# Submarine.net
KiCad netlist of a schematic drawn in Altium Designer
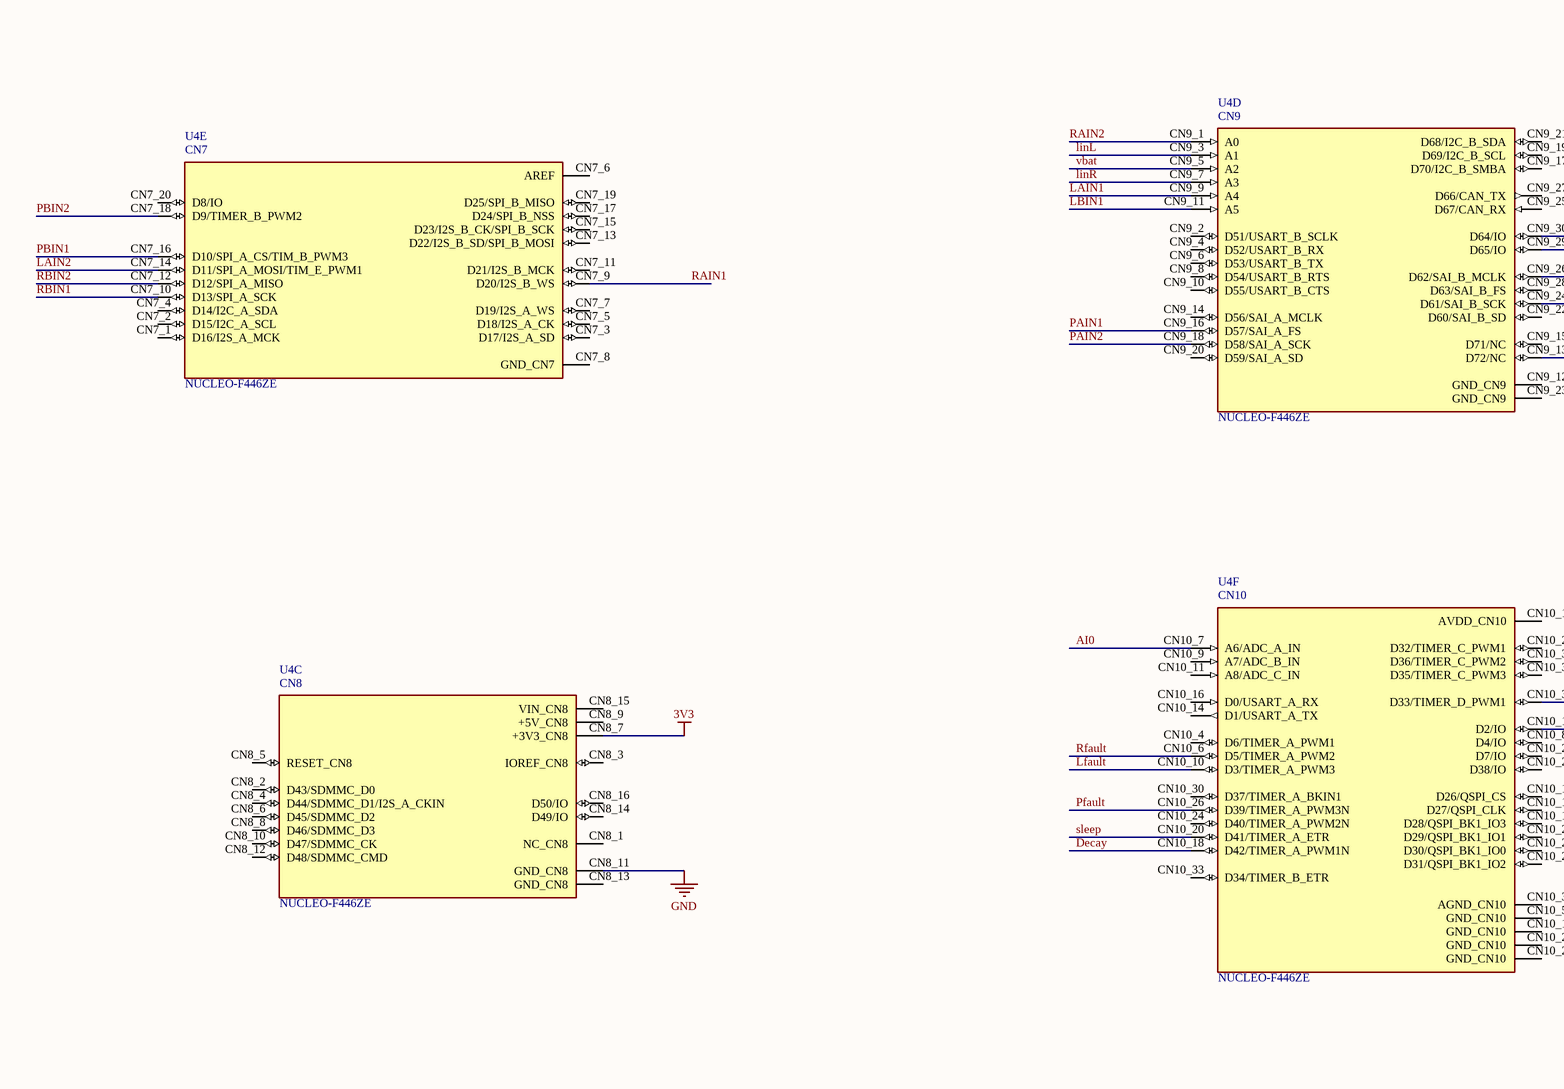
[diagram p0: Submarine.SchDoc, top left]
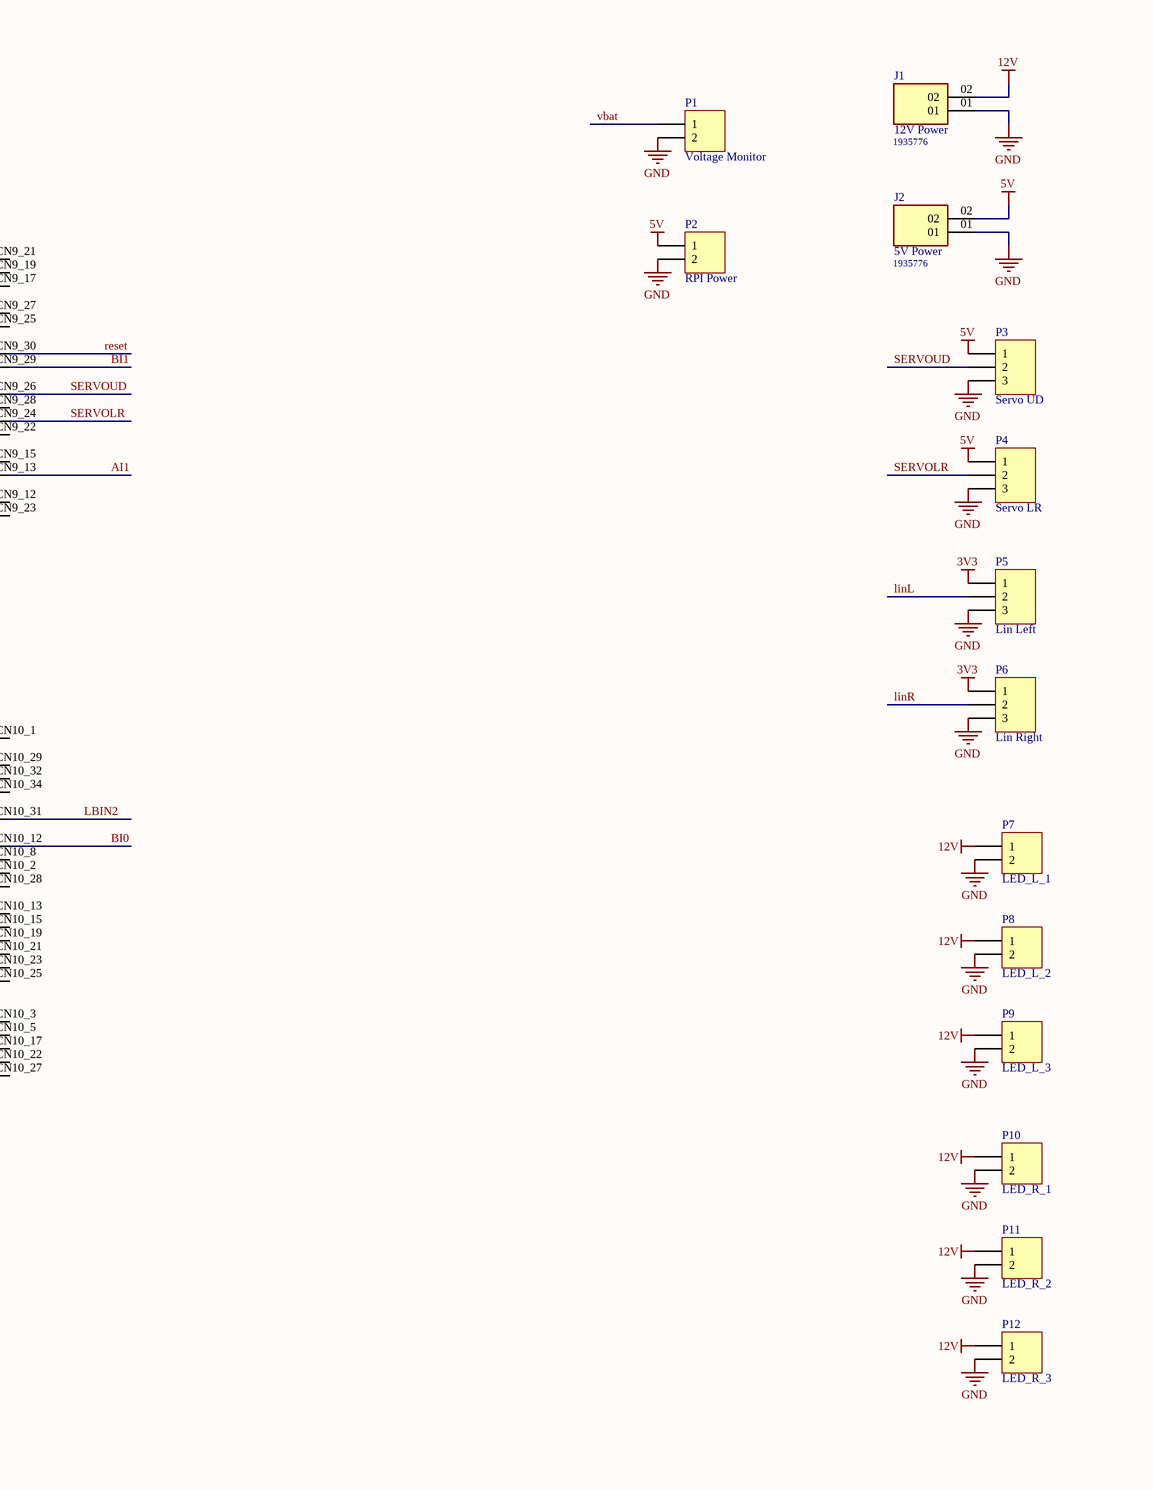
[diagram p1: Submarine.SchDoc, top middle]
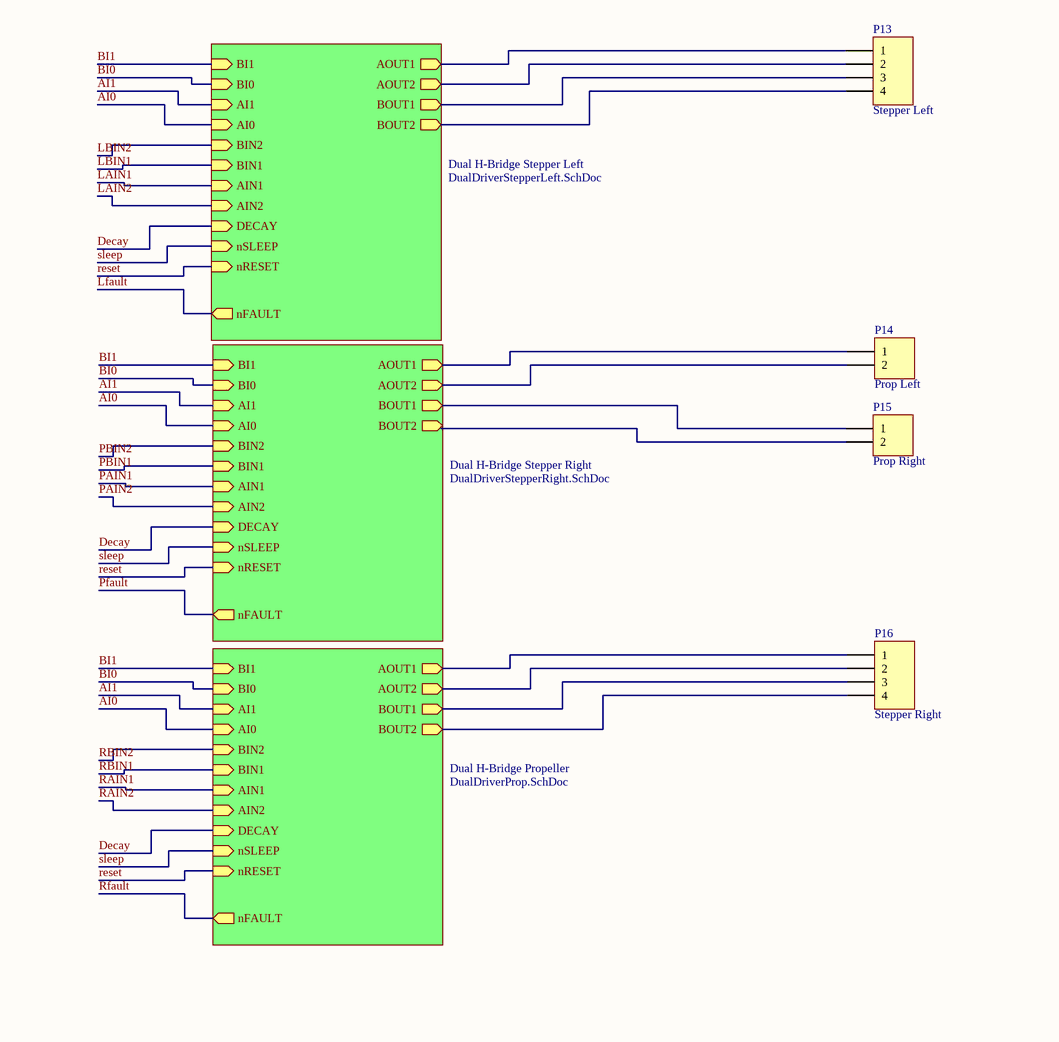
[diagram p2: Submarine.SchDoc, bottom middle]
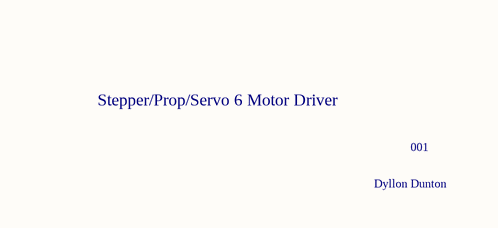
[diagram p3: Submarine.SchDoc, bottom right]

(export (version "E")
  (design (tool "Eeschema 10.0.6"))
  (components
    (comp (ref "J1")
      (value "12V Power")
      (footprint "PHOENIX_1935776")
      (fields (field (name "MP") "1935776"))
      (libsource (lib "1935776") (part "1935776"))
    )
    (comp (ref "J2")
      (value "5V Power")
      (footprint "PHOENIX_1935776")
      (fields (field (name "MP") "1935776"))
      (libsource (lib "1935776") (part "1935776"))
    )
    (comp (ref "P1")
      (value "Voltage Monitor")
      (footprint "HDR1X2")
      (description "Header, 2-Pin")
      (fields (field (name "PUBLISHER") "Altium Limited"))
      (libsource (lib "Miscellaneous Connectors") (part "Header 2"))
    )
    (comp (ref "P2")
      (value "RPI Power")
      (footprint "HDR1X2")
      (description "Header, 2-Pin")
      (fields (field (name "PUBLISHER") "Altium Limited"))
      (libsource (lib "Miscellaneous Connectors") (part "Header 2"))
    )
    (comp (ref "P3")
      (value "Servo UD")
      (footprint "HDR1X3")
      (description "Header, 3-Pin")
      (fields (field (name "PUBLISHER") "Altium Limited"))
      (libsource (lib "Miscellaneous Connectors") (part "Header 3"))
    )
    (comp (ref "P4")
      (value "Servo LR")
      (footprint "HDR1X3")
      (description "Header, 3-Pin")
      (fields (field (name "PUBLISHER") "Altium Limited"))
      (libsource (lib "Miscellaneous Connectors") (part "Header 3"))
    )
    (comp (ref "P5")
      (value "Lin Left")
      (footprint "HDR1X3")
      (description "Header, 3-Pin")
      (fields (field (name "PUBLISHER") "Altium Limited"))
      (libsource (lib "Miscellaneous Connectors") (part "Header 3"))
    )
    (comp (ref "P6")
      (value "Lin Right")
      (footprint "HDR1X3")
      (description "Header, 3-Pin")
      (fields (field (name "PUBLISHER") "Altium Limited"))
      (libsource (lib "Miscellaneous Connectors") (part "Header 3"))
    )
    (comp (ref "P7")
      (value "LED_L_1")
      (footprint "HDR1X2")
      (description "Header, 2-Pin")
      (fields (field (name "PUBLISHER") "Altium Limited"))
      (libsource (lib "Miscellaneous Connectors") (part "Header 2"))
    )
    (comp (ref "P8")
      (value "LED_L_2")
      (footprint "HDR1X2")
      (description "Header, 2-Pin")
      (fields (field (name "PUBLISHER") "Altium Limited"))
      (libsource (lib "Miscellaneous Connectors") (part "Header 2"))
    )
    (comp (ref "P9")
      (value "LED_L_3")
      (footprint "HDR1X2")
      (description "Header, 2-Pin")
      (fields (field (name "PUBLISHER") "Altium Limited"))
      (libsource (lib "Miscellaneous Connectors") (part "Header 2"))
    )
    (comp (ref "P10")
      (value "LED_R_1")
      (footprint "HDR1X2")
      (description "Header, 2-Pin")
      (fields (field (name "PUBLISHER") "Altium Limited"))
      (libsource (lib "Miscellaneous Connectors") (part "Header 2"))
    )
    (comp (ref "P11")
      (value "LED_R_2")
      (footprint "HDR1X2")
      (description "Header, 2-Pin")
      (fields (field (name "PUBLISHER") "Altium Limited"))
      (libsource (lib "Miscellaneous Connectors") (part "Header 2"))
    )
    (comp (ref "P12")
      (value "LED_R_3")
      (footprint "HDR1X2")
      (description "Header, 2-Pin")
      (fields (field (name "PUBLISHER") "Altium Limited"))
      (libsource (lib "Miscellaneous Connectors") (part "Header 2"))
    )
    (comp (ref "P13")
      (value "Stepper Left")
      (footprint "HDR1X4")
      (description "Header, 4-Pin")
      (fields (field (name "PUBLISHER") "Altium Limited"))
      (libsource (lib "Miscellaneous Connectors") (part "Header 4"))
    )
    (comp (ref "P14")
      (value "Prop Left")
      (footprint "HDR1X2")
      (description "Header, 2-Pin")
      (fields (field (name "PUBLISHER") "Altium Limited"))
      (libsource (lib "Miscellaneous Connectors") (part "Header 2"))
    )
    (comp (ref "P15")
      (value "Prop Right")
      (footprint "HDR1X2")
      (description "Header, 2-Pin")
      (fields (field (name "PUBLISHER") "Altium Limited"))
      (libsource (lib "Miscellaneous Connectors") (part "Header 2"))
    )
    (comp (ref "P16")
      (value "Stepper Right")
      (footprint "HDR1X4")
      (description "Header, 4-Pin")
      (fields (field (name "PUBLISHER") "Altium Limited"))
      (libsource (lib "Miscellaneous Connectors") (part "Header 4"))
    )
    (comp (ref "U4")
      (value "NUCLEO-F446ZE")
      (footprint "MODULE_NUCLEO-F446ZE")
      (fields (field (name "MF") "STMicroelectronics"))
      (libsource (lib "NUCLEO-F446ZE") (part "NUCLEO-F446ZE"))
    )
  )
  (nets
    (net (code "1") (name "/AI0") (class "Default")
      (node (ref "U4") (pin "CN10_7") (pinfunction "A6/ADC_A_IN_CN10_7") (pintype "input"))
    )
    (net (code "2") (name "/AI1") (class "Default")
      (node (ref "U4") (pin "CN9_13") (pinfunction "D72/NC_CN9_13") (pintype "bidirectional"))
    )
    (net (code "3") (name "/AOUT1") (class "Default")
      (node (ref "P16") (pin "1") (pinfunction "1_1") (pintype "passive"))
    )
    (net (code "4") (name "/AOUT1_1") (class "Default")
      (node (ref "P13") (pin "1") (pinfunction "1_1") (pintype "passive"))
    )
    (net (code "5") (name "/AOUT1_2") (class "Default")
      (node (ref "P14") (pin "1") (pinfunction "1_1") (pintype "passive"))
    )
    (net (code "6") (name "/AOUT2") (class "Default")
      (node (ref "P16") (pin "2") (pinfunction "2_2") (pintype "passive"))
    )
    (net (code "7") (name "/AOUT2_1") (class "Default")
      (node (ref "P13") (pin "2") (pinfunction "2_2") (pintype "passive"))
    )
    (net (code "8") (name "/AOUT2_2") (class "Default")
      (node (ref "P14") (pin "2") (pinfunction "2_2") (pintype "passive"))
    )
    (net (code "9") (name "/BI0") (class "Default")
      (node (ref "U4") (pin "CN10_12") (pinfunction "D2/IO_CN10_12") (pintype "bidirectional"))
    )
    (net (code "10") (name "/BI1") (class "Default")
      (node (ref "U4") (pin "CN9_29") (pinfunction "D65/IO_CN9_29") (pintype "bidirectional"))
    )
    (net (code "11") (name "/BOUT1") (class "Default")
      (node (ref "P15") (pin "1") (pinfunction "1_1") (pintype "passive"))
    )
    (net (code "12") (name "/BOUT1_1") (class "Default")
      (node (ref "P13") (pin "3") (pinfunction "3_3") (pintype "passive"))
    )
    (net (code "13") (name "/BOUT1_2") (class "Default")
      (node (ref "P16") (pin "3") (pinfunction "3_3") (pintype "passive"))
    )
    (net (code "15") (name "/BOUT2_1") (class "Default")
      (node (ref "P13") (pin "4") (pinfunction "4_4") (pintype "passive"))
    )
    (net (code "16") (name "/BOUT2_2") (class "Default")
      (node (ref "P16") (pin "4") (pinfunction "4_4") (pintype "passive"))
    )
    (net (code "17") (name "/Decay") (class "Default")
      (node (ref "U4") (pin "CN10_18") (pinfunction "D42/TIMER_A_PWM1N_CN10_18") (pintype "bidirectional"))
    )
    (net (code "18") (name "/LAIN1") (class "Default")
      (node (ref "U4") (pin "CN9_9") (pinfunction "A4_CN9_9") (pintype "input"))
    )
    (net (code "19") (name "/LAIN2") (class "Default")
      (node (ref "U4") (pin "CN7_14") (pinfunction "D11/SPI_A_MOSI/TIM_E_PWM1_CN7_14") (pintype "bidirectional"))
    )
    (net (code "20") (name "/LBIN1") (class "Default")
      (node (ref "U4") (pin "CN9_11") (pinfunction "A5_CN9_11") (pintype "input"))
    )
    (net (code "21") (name "/LBIN2") (class "Default")
      (node (ref "U4") (pin "CN10_31") (pinfunction "D33/TIMER_D_PWM1_CN10_31") (pintype "bidirectional"))
    )
    (net (code "22") (name "/Lfault") (class "Default")
      (node (ref "U4") (pin "CN10_10") (pinfunction "D3/TIMER_A_PWM3_CN10_10") (pintype "bidirectional"))
    )
    (net (code "23") (name "/PAIN1") (class "Default")
      (node (ref "U4") (pin "CN9_16") (pinfunction "D57/SAI_A_FS_CN9_16") (pintype "bidirectional"))
    )
    (net (code "24") (name "/PAIN2") (class "Default")
      (node (ref "U4") (pin "CN9_18") (pinfunction "D58/SAI_A_SCK_CN9_18") (pintype "bidirectional"))
    )
    (net (code "25") (name "/PBIN1") (class "Default")
      (node (ref "U4") (pin "CN7_16") (pinfunction "D10/SPI_A_CS/TIM_B_PWM3_CN7_16") (pintype "bidirectional"))
    )
    (net (code "26") (name "/PBIN2") (class "Default")
      (node (ref "U4") (pin "CN7_18") (pinfunction "D9/TIMER_B_PWM2_CN7_18") (pintype "bidirectional"))
    )
    (net (code "27") (name "/Pfault") (class "Default")
      (node (ref "U4") (pin "CN10_26") (pinfunction "D39/TIMER_A_PWM3N_CN10_26") (pintype "bidirectional"))
    )
    (net (code "28") (name "/RAIN1") (class "Default")
      (node (ref "U4") (pin "CN7_9") (pinfunction "D20/I2S_B_WS_CN7_9") (pintype "bidirectional"))
    )
    (net (code "29") (name "/RAIN2") (class "Default")
      (node (ref "U4") (pin "CN9_1") (pinfunction "A0_CN9_1") (pintype "input"))
    )
    (net (code "30") (name "/RBIN1") (class "Default")
      (node (ref "U4") (pin "CN7_10") (pinfunction "D13/SPI_A_SCK_CN7_10") (pintype "bidirectional"))
    )
    (net (code "31") (name "/RBIN2") (class "Default")
      (node (ref "U4") (pin "CN7_12") (pinfunction "D12/SPI_A_MISO_CN7_12") (pintype "bidirectional"))
    )
    (net (code "32") (name "/Rfault") (class "Default")
      (node (ref "U4") (pin "CN10_6") (pinfunction "D5/TIMER_A_PWM2_CN10_6") (pintype "bidirectional"))
    )
    (net (code "33") (name "/SERVOLR") (class "Default")
      (node (ref "P4") (pin "2") (pinfunction "2_2") (pintype "passive"))
      (node (ref "U4") (pin "CN9_24") (pinfunction "D61/SAI_B_SCK_CN9_24") (pintype "bidirectional"))
    )
    (net (code "34") (name "/SERVOUD") (class "Default")
      (node (ref "P3") (pin "2") (pinfunction "2_2") (pintype "passive"))
      (node (ref "U4") (pin "CN9_26") (pinfunction "D62/SAI_B_MCLK_CN9_26") (pintype "bidirectional"))
    )
    (net (code "35") (name "/linL") (class "Default")
      (node (ref "P5") (pin "2") (pinfunction "2_2") (pintype "passive"))
      (node (ref "U4") (pin "CN9_3") (pinfunction "A1_CN9_3") (pintype "input"))
    )
    (net (code "36") (name "/linR") (class "Default")
      (node (ref "P6") (pin "2") (pinfunction "2_2") (pintype "passive"))
      (node (ref "U4") (pin "CN9_7") (pinfunction "A3_CN9_7") (pintype "input"))
    )
    (net (code "37") (name "/reset") (class "Default")
      (node (ref "U4") (pin "CN9_30") (pinfunction "D64/IO_CN9_30") (pintype "bidirectional"))
    )
    (net (code "38") (name "/sleep") (class "Default")
      (node (ref "U4") (pin "CN10_20") (pinfunction "D41/TIMER_A_ETR_CN10_20") (pintype "bidirectional"))
    )
    (net (code "39") (name "/vbat") (class "Default")
      (node (ref "P1") (pin "1") (pinfunction "1_1") (pintype "passive"))
      (node (ref "U4") (pin "CN9_5") (pinfunction "A2_CN9_5") (pintype "input"))
    )
    (net (code "40") (name "3V3") (class "Default")
      (node (ref "P5") (pin "1") (pinfunction "1_1") (pintype "passive"))
      (node (ref "P6") (pin "1") (pinfunction "1_1") (pintype "passive"))
      (node (ref "U4") (pin "CN8_7") (pinfunction "+3V3_CN8_CN8_7") (pintype "power_in"))
    )
    (net (code "41") (name "5V") (class "Default")
      (node (ref "J2") (pin "02") (pinfunction "02_02") (pintype "passive"))
      (node (ref "P2") (pin "1") (pinfunction "1_1") (pintype "passive"))
      (node (ref "P3") (pin "1") (pinfunction "1_1") (pintype "passive"))
      (node (ref "P4") (pin "1") (pinfunction "1_1") (pintype "passive"))
    )
    (net (code "42") (name "12V") (class "Default")
      (node (ref "J1") (pin "02") (pinfunction "02_02") (pintype "passive"))
      (node (ref "P10") (pin "1") (pinfunction "1_1") (pintype "passive"))
      (node (ref "P11") (pin "1") (pinfunction "1_1") (pintype "passive"))
      (node (ref "P12") (pin "1") (pinfunction "1_1") (pintype "passive"))
      (node (ref "P7") (pin "1") (pinfunction "1_1") (pintype "passive"))
      (node (ref "P8") (pin "1") (pinfunction "1_1") (pintype "passive"))
      (node (ref "P9") (pin "1") (pinfunction "1_1") (pintype "passive"))
    )
    (net (code "43") (name "GND") (class "Default")
      (node (ref "J1") (pin "01") (pinfunction "01_01") (pintype "passive"))
      (node (ref "J2") (pin "01") (pinfunction "01_01") (pintype "passive"))
      (node (ref "P1") (pin "2") (pinfunction "2_2") (pintype "passive"))
      (node (ref "P10") (pin "2") (pinfunction "2_2") (pintype "passive"))
      (node (ref "P11") (pin "2") (pinfunction "2_2") (pintype "passive"))
      (node (ref "P12") (pin "2") (pinfunction "2_2") (pintype "passive"))
      (node (ref "P2") (pin "2") (pinfunction "2_2") (pintype "passive"))
      (node (ref "P3") (pin "3") (pinfunction "3_3") (pintype "passive"))
      (node (ref "P4") (pin "3") (pinfunction "3_3") (pintype "passive"))
      (node (ref "P5") (pin "3") (pinfunction "3_3") (pintype "passive"))
      (node (ref "P6") (pin "3") (pinfunction "3_3") (pintype "passive"))
      (node (ref "P7") (pin "2") (pinfunction "2_2") (pintype "passive"))
      (node (ref "P8") (pin "2") (pinfunction "2_2") (pintype "passive"))
      (node (ref "P9") (pin "2") (pinfunction "2_2") (pintype "passive"))
      (node (ref "U4") (pin "CN8_11") (pinfunction "GND_CN8_CN8_11") (pintype "power_in"))
    )
    (net (code "44") (name "unconnected-(P15-Pad2)") (class "Default")
      (node (ref "P15") (pin "2") (pinfunction "2_2") (pintype "passive"))
    )
    (net (code "45") (name "unconnected-(U4C-+5V_CN8-PadCN8_9)") (class "Default")
      (node (ref "U4") (pin "CN8_9") (pinfunction "+5V_CN8_CN8_9") (pintype "power_in"))
    )
    (net (code "46") (name "unconnected-(U4C-D43{slash}SDMMC_D0-PadCN8_2)") (class "Default")
      (node (ref "U4") (pin "CN8_2") (pinfunction "D43/SDMMC_D0_CN8_2") (pintype "bidirectional"))
    )
    (net (code "47") (name "unconnected-(U4C-D44{slash}SDMMC_D1{slash}I2S_A_CKIN-PadCN8_4)") (class "Default")
      (node (ref "U4") (pin "CN8_4") (pinfunction "D44/SDMMC_D1/I2S_A_CKIN_CN8_4") (pintype "bidirectional"))
    )
    (net (code "48") (name "unconnected-(U4C-D45{slash}SDMMC_D2-PadCN8_6)") (class "Default")
      (node (ref "U4") (pin "CN8_6") (pinfunction "D45/SDMMC_D2_CN8_6") (pintype "bidirectional"))
    )
    (net (code "49") (name "unconnected-(U4C-D46{slash}SDMMC_D3-PadCN8_8)") (class "Default")
      (node (ref "U4") (pin "CN8_8") (pinfunction "D46/SDMMC_D3_CN8_8") (pintype "bidirectional"))
    )
    (net (code "50") (name "unconnected-(U4C-D47{slash}SDMMC_CK-PadCN8_10)") (class "Default")
      (node (ref "U4") (pin "CN8_10") (pinfunction "D47/SDMMC_CK_CN8_10") (pintype "bidirectional"))
    )
    (net (code "51") (name "unconnected-(U4C-D48{slash}SDMMC_CMD-PadCN8_12)") (class "Default")
      (node (ref "U4") (pin "CN8_12") (pinfunction "D48/SDMMC_CMD_CN8_12") (pintype "bidirectional"))
    )
    (net (code "52") (name "unconnected-(U4C-D49{slash}IO-PadCN8_14)") (class "Default")
      (node (ref "U4") (pin "CN8_14") (pinfunction "D49/IO_CN8_14") (pintype "bidirectional"))
    )
    (net (code "53") (name "unconnected-(U4C-D50{slash}IO-PadCN8_16)") (class "Default")
      (node (ref "U4") (pin "CN8_16") (pinfunction "D50/IO_CN8_16") (pintype "bidirectional"))
    )
    (net (code "54") (name "unconnected-(U4C-GND_CN8-PadCN8_13)") (class "Default")
      (node (ref "U4") (pin "CN8_13") (pinfunction "GND_CN8_CN8_13") (pintype "power_in"))
    )
    (net (code "55") (name "unconnected-(U4C-IOREF_CN8-PadCN8_3)") (class "Default")
      (node (ref "U4") (pin "CN8_3") (pinfunction "IOREF_CN8_CN8_3") (pintype "bidirectional"))
    )
    (net (code "56") (name "unconnected-(U4C-NC_CN8-PadCN8_1)") (class "Default")
      (node (ref "U4") (pin "CN8_1") (pinfunction "NC_CN8_CN8_1") (pintype "passive"))
    )
    (net (code "57") (name "unconnected-(U4C-RESET_CN8-PadCN8_5)") (class "Default")
      (node (ref "U4") (pin "CN8_5") (pinfunction "RESET_CN8_CN8_5") (pintype "bidirectional"))
    )
    (net (code "58") (name "unconnected-(U4C-VIN_CN8-PadCN8_15)") (class "Default")
      (node (ref "U4") (pin "CN8_15") (pinfunction "VIN_CN8_CN8_15") (pintype "power_in"))
    )
    (net (code "59") (name "unconnected-(U4D-D51{slash}USART_B_SCLK-PadCN9_2)") (class "Default")
      (node (ref "U4") (pin "CN9_2") (pinfunction "D51/USART_B_SCLK_CN9_2") (pintype "bidirectional"))
    )
    (net (code "60") (name "unconnected-(U4D-D52{slash}USART_B_RX-PadCN9_4)") (class "Default")
      (node (ref "U4") (pin "CN9_4") (pinfunction "D52/USART_B_RX_CN9_4") (pintype "bidirectional"))
    )
    (net (code "61") (name "unconnected-(U4D-D53{slash}USART_B_TX-PadCN9_6)") (class "Default")
      (node (ref "U4") (pin "CN9_6") (pinfunction "D53/USART_B_TX_CN9_6") (pintype "bidirectional"))
    )
    (net (code "62") (name "unconnected-(U4D-D54{slash}USART_B_RTS-PadCN9_8)") (class "Default")
      (node (ref "U4") (pin "CN9_8") (pinfunction "D54/USART_B_RTS_CN9_8") (pintype "bidirectional"))
    )
    (net (code "63") (name "unconnected-(U4D-D55{slash}USART_B_CTS-PadCN9_10)") (class "Default")
      (node (ref "U4") (pin "CN9_10") (pinfunction "D55/USART_B_CTS_CN9_10") (pintype "bidirectional"))
    )
    (net (code "64") (name "unconnected-(U4D-D56{slash}SAI_A_MCLK-PadCN9_14)") (class "Default")
      (node (ref "U4") (pin "CN9_14") (pinfunction "D56/SAI_A_MCLK_CN9_14") (pintype "bidirectional"))
    )
    (net (code "65") (name "unconnected-(U4D-D59{slash}SAI_A_SD-PadCN9_20)") (class "Default")
      (node (ref "U4") (pin "CN9_20") (pinfunction "D59/SAI_A_SD_CN9_20") (pintype "bidirectional"))
    )
    (net (code "66") (name "unconnected-(U4D-D60{slash}SAI_B_SD-PadCN9_22)") (class "Default")
      (node (ref "U4") (pin "CN9_22") (pinfunction "D60/SAI_B_SD_CN9_22") (pintype "bidirectional"))
    )
    (net (code "67") (name "unconnected-(U4D-D63{slash}SAI_B_FS-PadCN9_28)") (class "Default")
      (node (ref "U4") (pin "CN9_28") (pinfunction "D63/SAI_B_FS_CN9_28") (pintype "bidirectional"))
    )
    (net (code "68") (name "unconnected-(U4D-D66{slash}CAN_TX-PadCN9_27)") (class "Default")
      (node (ref "U4") (pin "CN9_27") (pinfunction "D66/CAN_TX_CN9_27") (pintype "output"))
    )
    (net (code "69") (name "unconnected-(U4D-D67{slash}CAN_RX-PadCN9_25)") (class "Default")
      (node (ref "U4") (pin "CN9_25") (pinfunction "D67/CAN_RX_CN9_25") (pintype "input"))
    )
    (net (code "70") (name "unconnected-(U4D-D68{slash}I2C_B_SDA-PadCN9_21)") (class "Default")
      (node (ref "U4") (pin "CN9_21") (pinfunction "D68/I2C_B_SDA_CN9_21") (pintype "bidirectional"))
    )
    (net (code "71") (name "unconnected-(U4D-D69{slash}I2C_B_SCL-PadCN9_19)") (class "Default")
      (node (ref "U4") (pin "CN9_19") (pinfunction "D69/I2C_B_SCL_CN9_19") (pintype "bidirectional"))
    )
    (net (code "72") (name "unconnected-(U4D-D70{slash}I2C_B_SMBA-PadCN9_17)") (class "Default")
      (node (ref "U4") (pin "CN9_17") (pinfunction "D70/I2C_B_SMBA_CN9_17") (pintype "bidirectional"))
    )
    (net (code "73") (name "unconnected-(U4D-D71{slash}NC-PadCN9_15)") (class "Default")
      (node (ref "U4") (pin "CN9_15") (pinfunction "D71/NC_CN9_15") (pintype "bidirectional"))
    )
    (net (code "74") (name "unconnected-(U4D-GND_CN9-PadCN9_12)") (class "Default")
      (node (ref "U4") (pin "CN9_12") (pinfunction "GND_CN9_CN9_12") (pintype "power_in"))
    )
    (net (code "75") (name "unconnected-(U4D-GND_CN9-PadCN9_23)") (class "Default")
      (node (ref "U4") (pin "CN9_23") (pinfunction "GND_CN9_CN9_23") (pintype "power_in"))
    )
    (net (code "76") (name "unconnected-(U4E-AREF-PadCN7_6)") (class "Default")
      (node (ref "U4") (pin "CN7_6") (pinfunction "AREF_CN7_6") (pintype "power_in"))
    )
    (net (code "77") (name "unconnected-(U4E-D8{slash}IO-PadCN7_20)") (class "Default")
      (node (ref "U4") (pin "CN7_20") (pinfunction "D8/IO_CN7_20") (pintype "bidirectional"))
    )
    (net (code "78") (name "unconnected-(U4E-D14{slash}I2C_A_SDA-PadCN7_4)") (class "Default")
      (node (ref "U4") (pin "CN7_4") (pinfunction "D14/I2C_A_SDA_CN7_4") (pintype "bidirectional"))
    )
    (net (code "79") (name "unconnected-(U4E-D15{slash}I2C_A_SCL-PadCN7_2)") (class "Default")
      (node (ref "U4") (pin "CN7_2") (pinfunction "D15/I2C_A_SCL_CN7_2") (pintype "bidirectional"))
    )
    (net (code "80") (name "unconnected-(U4E-D16{slash}I2S_A_MCK-PadCN7_1)") (class "Default")
      (node (ref "U4") (pin "CN7_1") (pinfunction "D16/I2S_A_MCK_CN7_1") (pintype "bidirectional"))
    )
    (net (code "81") (name "unconnected-(U4E-D17{slash}I2S_A_SD-PadCN7_3)") (class "Default")
      (node (ref "U4") (pin "CN7_3") (pinfunction "D17/I2S_A_SD_CN7_3") (pintype "bidirectional"))
    )
    (net (code "82") (name "unconnected-(U4E-D18{slash}I2S_A_CK-PadCN7_5)") (class "Default")
      (node (ref "U4") (pin "CN7_5") (pinfunction "D18/I2S_A_CK_CN7_5") (pintype "bidirectional"))
    )
    (net (code "83") (name "unconnected-(U4E-D19{slash}I2S_A_WS-PadCN7_7)") (class "Default")
      (node (ref "U4") (pin "CN7_7") (pinfunction "D19/I2S_A_WS_CN7_7") (pintype "bidirectional"))
    )
    (net (code "84") (name "unconnected-(U4E-D21{slash}I2S_B_MCK-PadCN7_11)") (class "Default")
      (node (ref "U4") (pin "CN7_11") (pinfunction "D21/I2S_B_MCK_CN7_11") (pintype "bidirectional"))
    )
    (net (code "85") (name "unconnected-(U4E-D22{slash}I2S_B_SD{slash}SPI_B_MOSI-PadCN7_13)") (class "Default")
      (node (ref "U4") (pin "CN7_13") (pinfunction "D22/I2S_B_SD/SPI_B_MOSI_CN7_13") (pintype "bidirectional"))
    )
    (net (code "86") (name "unconnected-(U4E-D23{slash}I2S_B_CK{slash}SPI_B_SCK-PadCN7_15)") (class "Default")
      (node (ref "U4") (pin "CN7_15") (pinfunction "D23/I2S_B_CK/SPI_B_SCK_CN7_15") (pintype "bidirectional"))
    )
    (net (code "87") (name "unconnected-(U4E-D24{slash}SPI_B_NSS-PadCN7_17)") (class "Default")
      (node (ref "U4") (pin "CN7_17") (pinfunction "D24/SPI_B_NSS_CN7_17") (pintype "bidirectional"))
    )
    (net (code "88") (name "unconnected-(U4E-D25{slash}SPI_B_MISO-PadCN7_19)") (class "Default")
      (node (ref "U4") (pin "CN7_19") (pinfunction "D25/SPI_B_MISO_CN7_19") (pintype "bidirectional"))
    )
    (net (code "89") (name "unconnected-(U4E-GND_CN7-PadCN7_8)") (class "Default")
      (node (ref "U4") (pin "CN7_8") (pinfunction "GND_CN7_CN7_8") (pintype "power_in"))
    )
    (net (code "90") (name "unconnected-(U4F-A7{slash}ADC_B_IN-PadCN10_9)") (class "Default")
      (node (ref "U4") (pin "CN10_9") (pinfunction "A7/ADC_B_IN_CN10_9") (pintype "input"))
    )
    (net (code "91") (name "unconnected-(U4F-A8{slash}ADC_C_IN-PadCN10_11)") (class "Default")
      (node (ref "U4") (pin "CN10_11") (pinfunction "A8/ADC_C_IN_CN10_11") (pintype "input"))
    )
    (net (code "92") (name "unconnected-(U4F-AGND_CN10-PadCN10_3)") (class "Default")
      (node (ref "U4") (pin "CN10_3") (pinfunction "AGND_CN10_CN10_3") (pintype "power_in"))
    )
    (net (code "93") (name "unconnected-(U4F-AVDD_CN10-PadCN10_1)") (class "Default")
      (node (ref "U4") (pin "CN10_1") (pinfunction "AVDD_CN10_CN10_1") (pintype "power_in"))
    )
    (net (code "94") (name "unconnected-(U4F-D0{slash}USART_A_RX-PadCN10_16)") (class "Default")
      (node (ref "U4") (pin "CN10_16") (pinfunction "D0/USART_A_RX_CN10_16") (pintype "input"))
    )
    (net (code "95") (name "unconnected-(U4F-D1{slash}USART_A_TX-PadCN10_14)") (class "Default")
      (node (ref "U4") (pin "CN10_14") (pinfunction "D1/USART_A_TX_CN10_14") (pintype "output"))
    )
    (net (code "96") (name "unconnected-(U4F-D4{slash}IO-PadCN10_8)") (class "Default")
      (node (ref "U4") (pin "CN10_8") (pinfunction "D4/IO_CN10_8") (pintype "bidirectional"))
    )
    (net (code "97") (name "unconnected-(U4F-D6{slash}TIMER_A_PWM1-PadCN10_4)") (class "Default")
      (node (ref "U4") (pin "CN10_4") (pinfunction "D6/TIMER_A_PWM1_CN10_4") (pintype "bidirectional"))
    )
    (net (code "98") (name "unconnected-(U4F-D7{slash}IO-PadCN10_2)") (class "Default")
      (node (ref "U4") (pin "CN10_2") (pinfunction "D7/IO_CN10_2") (pintype "bidirectional"))
    )
    (net (code "99") (name "unconnected-(U4F-D26{slash}QSPI_CS-PadCN10_13)") (class "Default")
      (node (ref "U4") (pin "CN10_13") (pinfunction "D26/QSPI_CS_CN10_13") (pintype "bidirectional"))
    )
    (net (code "100") (name "unconnected-(U4F-D27{slash}QSPI_CLK-PadCN10_15)") (class "Default")
      (node (ref "U4") (pin "CN10_15") (pinfunction "D27/QSPI_CLK_CN10_15") (pintype "bidirectional"))
    )
    (net (code "101") (name "unconnected-(U4F-D28{slash}QSPI_BK1_IO3-PadCN10_19)") (class "Default")
      (node (ref "U4") (pin "CN10_19") (pinfunction "D28/QSPI_BK1_IO3_CN10_19") (pintype "bidirectional"))
    )
    (net (code "102") (name "unconnected-(U4F-D29{slash}QSPI_BK1_IO1-PadCN10_21)") (class "Default")
      (node (ref "U4") (pin "CN10_21") (pinfunction "D29/QSPI_BK1_IO1_CN10_21") (pintype "bidirectional"))
    )
    (net (code "103") (name "unconnected-(U4F-D30{slash}QSPI_BK1_IO0-PadCN10_23)") (class "Default")
      (node (ref "U4") (pin "CN10_23") (pinfunction "D30/QSPI_BK1_IO0_CN10_23") (pintype "bidirectional"))
    )
    (net (code "104") (name "unconnected-(U4F-D31{slash}QSPI_BK1_IO2-PadCN10_25)") (class "Default")
      (node (ref "U4") (pin "CN10_25") (pinfunction "D31/QSPI_BK1_IO2_CN10_25") (pintype "bidirectional"))
    )
    (net (code "105") (name "unconnected-(U4F-D32{slash}TIMER_C_PWM1-PadCN10_29)") (class "Default")
      (node (ref "U4") (pin "CN10_29") (pinfunction "D32/TIMER_C_PWM1_CN10_29") (pintype "bidirectional"))
    )
    (net (code "106") (name "unconnected-(U4F-D34{slash}TIMER_B_ETR-PadCN10_33)") (class "Default")
      (node (ref "U4") (pin "CN10_33") (pinfunction "D34/TIMER_B_ETR_CN10_33") (pintype "bidirectional"))
    )
    (net (code "107") (name "unconnected-(U4F-D35{slash}TIMER_C_PWM3-PadCN10_34)") (class "Default")
      (node (ref "U4") (pin "CN10_34") (pinfunction "D35/TIMER_C_PWM3_CN10_34") (pintype "bidirectional"))
    )
    (net (code "108") (name "unconnected-(U4F-D36{slash}TIMER_C_PWM2-PadCN10_32)") (class "Default")
      (node (ref "U4") (pin "CN10_32") (pinfunction "D36/TIMER_C_PWM2_CN10_32") (pintype "bidirectional"))
    )
    (net (code "109") (name "unconnected-(U4F-D37{slash}TIMER_A_BKIN1-PadCN10_30)") (class "Default")
      (node (ref "U4") (pin "CN10_30") (pinfunction "D37/TIMER_A_BKIN1_CN10_30") (pintype "bidirectional"))
    )
    (net (code "110") (name "unconnected-(U4F-D38{slash}IO-PadCN10_28)") (class "Default")
      (node (ref "U4") (pin "CN10_28") (pinfunction "D38/IO_CN10_28") (pintype "bidirectional"))
    )
    (net (code "111") (name "unconnected-(U4F-D40{slash}TIMER_A_PWM2N-PadCN10_24)") (class "Default")
      (node (ref "U4") (pin "CN10_24") (pinfunction "D40/TIMER_A_PWM2N_CN10_24") (pintype "bidirectional"))
    )
    (net (code "112") (name "unconnected-(U4F-GND_CN10-PadCN10_5)") (class "Default")
      (node (ref "U4") (pin "CN10_5") (pinfunction "GND_CN10_CN10_5") (pintype "power_in"))
    )
    (net (code "113") (name "unconnected-(U4F-GND_CN10-PadCN10_17)") (class "Default")
      (node (ref "U4") (pin "CN10_17") (pinfunction "GND_CN10_CN10_17") (pintype "power_in"))
    )
    (net (code "114") (name "unconnected-(U4F-GND_CN10-PadCN10_22)") (class "Default")
      (node (ref "U4") (pin "CN10_22") (pinfunction "GND_CN10_CN10_22") (pintype "power_in"))
    )
    (net (code "115") (name "unconnected-(U4F-GND_CN10-PadCN10_27)") (class "Default")
      (node (ref "U4") (pin "CN10_27") (pinfunction "GND_CN10_CN10_27") (pintype "power_in"))
    )
  )
)
